# nguyenly.net
KiCad netlist of a schematic drawn in Altium Designer
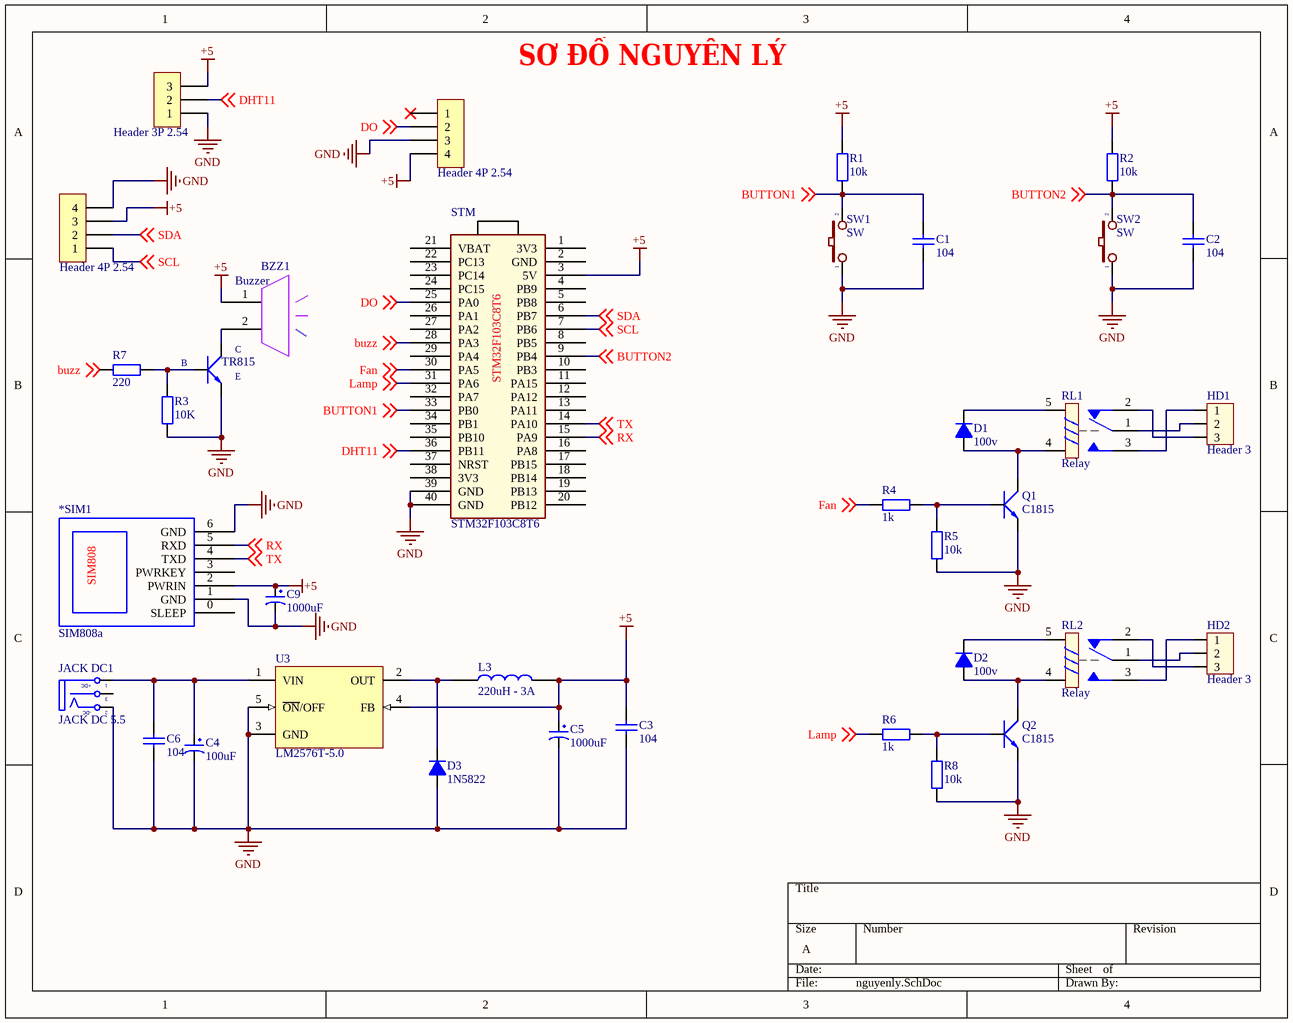
[diagram p0: nguyenly.SchDoc]

(export (version "E")
  (design (tool "Eeschema 10.0.6"))
  (components
    (comp (ref "*SIM1")
      (value "SIM808a")
      (footprint "PCBComponent_1")
      (libsource (lib "SIM808") (part "SIM808a"))
    )
    (comp (ref "BZZ1")
      (value "Buzzer")
      (footprint "buzzer 5V")
      (libsource (lib "My library altium") (part "Buzzer"))
    )
    (comp (ref "C1")
      (value "104")
      (footprint "tu gom")
      (description "Cắm")
      (libsource (lib "Altium_Lib_by_KhueNguyenCreator") (part "Tu gom 104 50V"))
    )
    (comp (ref "C2")
      (value "104")
      (footprint "tu gom")
      (description "Cắm")
      (libsource (lib "Altium_Lib_by_KhueNguyenCreator") (part "Tu gom 104 50V"))
    )
    (comp (ref "C3")
      (value "104")
      (footprint "tu gom")
      (description "Cắm")
      (libsource (lib "Altium_Lib_by_KhueNguyenCreator") (part "Tu gom 104 50V"))
    )
    (comp (ref "C4")
      (value "100uF")
      (footprint "tu hoa 5mm")
      (description "Cắm")
      (libsource (lib "Altium_Lib_by_KhueNguyenCreator") (part "Tu Hoa 100uF 16V 5x7"))
    )
    (comp (ref "C5")
      (value "1000uF")
      (footprint "tu hoa 5mm")
      (description "Cắm")
      (libsource (lib "Altium_Lib_by_KhueNguyenCreator") (part "Tu Hoa 100uF 16V 5x7"))
    )
    (comp (ref "C6")
      (value "104")
      (footprint "tu gom")
      (description "Cắm")
      (libsource (lib "Altium_Lib_by_KhueNguyenCreator") (part "Tu gom 104 50V"))
    )
    (comp (ref "C9")
      (value "1000uF")
      (footprint "tu hoa 13mm")
      (description "Cắm")
      (libsource (lib "Altium_Lib_by_KhueNguyenCreator") (part "Tu Hoa 1000uF 25V 13x21"))
    )
    (comp (ref "D1")
      (value "100v")
      (footprint "DIODE 1A")
      (description "Cắm")
      (libsource (lib "Altium_Lib_by_KhueNguyenCreator") (part "Diode 1N4007"))
    )
    (comp (ref "D2")
      (value "100v")
      (footprint "DIODE 1A")
      (description "Cắm")
      (libsource (lib "Altium_Lib_by_KhueNguyenCreator") (part "Diode 1N4007"))
    )
    (comp (ref "D3")
      (value "1N5822")
      (footprint "D5A")
      (description "Diode 5A")
      (libsource (lib "syhaunguyen") (part "D5A"))
    )
    (comp (ref "H1")
      (value "Header 4P 2.54")
      (footprint "XH2.54M-4")
      (description "Cắm")
      (libsource (lib "Altium_Lib_by_KhueNguyenCreator") (part "Header 4P 2.54 Duc Thang"))
    )
    (comp (ref "H2")
      (value "Header 3P 2.54")
      (footprint "XH2.54M-3")
      (description "Cắm")
      (libsource (lib "Altium_Lib_by_KhueNguyenCreator") (part "Header 3P 2.54 Duc Thang"))
    )
    (comp (ref "H3")
      (value "Header 4P 2.54")
      (footprint "XH2.54M-4")
      (description "Cắm")
      (libsource (lib "") (part "Header 4P 2.54 Duc Thang_1"))
    )
    (comp (ref "HD1")
      (value "Header 3")
      (footprint "HED3")
      (description "Header 3 (Green)")
      (libsource (lib "My library altium") (part "Header 3"))
    )
    (comp (ref "HD2")
      (value "Header 3")
      (footprint "HED3")
      (description "Header 3 (Green)")
      (libsource (lib "My library altium") (part "Header 3"))
    )
    (comp (ref "JACK DC1")
      (value "JACK DC 5.5")
      (footprint "JACK DC 5.5")
      (libsource (lib "Altium_Lib_by_KhueNguyenCreator") (part "JACK DC 5.5"))
    )
    (comp (ref "L3")
      (value "220uH - 3A")
      (footprint "CUON CAM 100uH3A")
      (description "Cắm")
      (libsource (lib "Altium_Lib_by_KhueNguyenCreator") (part "CUON CAM 470uH DIP"))
    )
    (comp (ref "Q1")
      (value "C1815")
      (footprint "TO92")
      (description "NPN transistor")
      (libsource (lib "Altium_Lib_by_KhueNguyenCreator") (part "Trans C1815 DIP"))
    )
    (comp (ref "Q2")
      (value "C1815")
      (footprint "TO92")
      (description "NPN transistor")
      (libsource (lib "Altium_Lib_by_KhueNguyenCreator") (part "Trans C1815 DIP"))
    )
    (comp (ref "R1")
      (value "10k")
      (footprint "tro vach 1/2w")
      (description "Cắm")
      (libsource (lib "Altium_Lib_by_KhueNguyenCreator") (part "Tro Vach 1/2W 5% 1k"))
    )
    (comp (ref "R2")
      (value "10k")
      (footprint "tro vach 1/2w")
      (description "Cắm")
      (libsource (lib "Altium_Lib_by_KhueNguyenCreator") (part "Tro Vach 1/2W 5% 1k"))
    )
    (comp (ref "R3")
      (value "10K")
      (footprint "tro vach 1/2w")
      (description "Cắm")
      (libsource (lib "Altium_Lib_by_KhueNguyenCreator") (part "Tro Vach 1/2W 5% 1k"))
    )
    (comp (ref "R4")
      (value "1k")
      (footprint "tro vach 1/2w")
      (description "Cắm")
      (libsource (lib "Altium_Lib_by_KhueNguyenCreator") (part "Tro Vach 1/2W 5% 1k"))
    )
    (comp (ref "R5")
      (value "10k")
      (footprint "tro vach 1/2w")
      (description "Cắm")
      (libsource (lib "Altium_Lib_by_KhueNguyenCreator") (part "Tro Vach 1/2W 5% 1k"))
    )
    (comp (ref "R6")
      (value "1k")
      (footprint "tro vach 1/2w")
      (description "Cắm")
      (libsource (lib "Altium_Lib_by_KhueNguyenCreator") (part "Tro Vach 1/2W 5% 1k"))
    )
    (comp (ref "R7")
      (value "220")
      (footprint "tro vach 1/2w")
      (description "Cắm")
      (libsource (lib "Altium_Lib_by_KhueNguyenCreator") (part "Tro Vach 1/2W 5% 1k"))
    )
    (comp (ref "R8")
      (value "10k")
      (footprint "tro vach 1/2w")
      (description "Cắm")
      (libsource (lib "Altium_Lib_by_KhueNguyenCreator") (part "Tro Vach 1/2W 5% 1k"))
    )
    (comp (ref "RL1")
      (value "Relay")
      (footprint "Relay 5 Chan SRD")
      (description "Relay 5 Chan")
      (libsource (lib "Altium_Lib_by_KhueNguyenCreator") (part "Relay 5 Chan SRD"))
    )
    (comp (ref "RL2")
      (value "Relay")
      (footprint "Relay 5 Chan SRD")
      (description "Relay 5 Chan")
      (libsource (lib "Altium_Lib_by_KhueNguyenCreator") (part "Relay 5 Chan SRD"))
    )
    (comp (ref "STA.TR1")
      (value "TR815")
      (footprint "QTO-92")
      (description "NPN 600mW, ECB")
      (libsource (lib "My library altium") (part "C1815"))
    )
    (comp (ref "STM")
      (value "STM32F103C8T6")
      (footprint "PCBComponent_1")
      (libsource (lib "STM32F103C8T6") (part "STM32"))
    )
    (comp (ref "SW1")
      (value "SW")
      (footprint "SW2")
      (description "Switch button 2 pin")
      (libsource (lib "syhaunguyen") (part "SW2"))
    )
    (comp (ref "SW2")
      (value "SW")
      (footprint "SW2")
      (description "Switch button 2 pin")
      (libsource (lib "syhaunguyen") (part "SW2"))
    )
    (comp (ref "U3")
      (value "LM2576T-5.0")
      (footprint "LM2576t")
      (description "SIMPLE SWITCHER; 3A Step-Down Voltage Regulator")
      (fields
        (field (name "MANUFACTURER") "National Semiconductor")
        (field (name "DIGIKEYPARTNUMBER") "LM2576T-5.0-ND")
        (field (name "PUBLISHER") "Altium Limited")
      )
      (libsource (lib "My library altium") (part "LM2576T-5.0"))
    )
  )
  (nets
    (net (code "1") (name "+5") (class "Default")
      (node (ref "*SIM1") (pin "2") (pinfunction "PWRIN_2") (pintype "passive"))
      (node (ref "BZZ1") (pin "1") (pinfunction "1_1") (pintype "passive"))
      (node (ref "C3") (pin "1") (pinfunction "1_1") (pintype "passive"))
      (node (ref "C5") (pin "1") (pinfunction "1_1") (pintype "passive"))
      (node (ref "C9") (pin "1") (pinfunction "1_1") (pintype "passive"))
      (node (ref "H1") (pin "4") (pinfunction "4_4") (pintype "passive"))
      (node (ref "H2") (pin "3") (pinfunction "3_3") (pintype "passive"))
      (node (ref "H3") (pin "3") (pinfunction "3_3") (pintype "passive"))
      (node (ref "L3") (pin "2") (pinfunction "2_2") (pintype "passive"))
      (node (ref "R1") (pin "2") (pinfunction "2_2") (pintype "passive"))
      (node (ref "R2") (pin "2") (pinfunction "2_2") (pintype "passive"))
      (node (ref "STM") (pin "3") (pinfunction "5V_3") (pintype "passive"))
      (node (ref "U3") (pin "4") (pinfunction "FB_4") (pintype "input"))
    )
    (net (code "2") (name "BUTTON1") (class "Default")
      (node (ref "C1") (pin "1") (pinfunction "1_1") (pintype "passive"))
      (node (ref "R1") (pin "1") (pinfunction "1_1") (pintype "passive"))
      (node (ref "STM") (pin "33") (pinfunction "PB0_33") (pintype "passive"))
      (node (ref "SW1") (pin "2") (pinfunction "2_2") (pintype "passive"))
    )
    (net (code "3") (name "BUTTON2") (class "Default")
      (node (ref "C2") (pin "1") (pinfunction "1_1") (pintype "passive"))
      (node (ref "R2") (pin "1") (pinfunction "1_1") (pintype "passive"))
      (node (ref "STM") (pin "9") (pinfunction "PB4_9") (pintype "passive"))
      (node (ref "SW2") (pin "2") (pinfunction "2_2") (pintype "passive"))
    )
    (net (code "4") (name "DHT11") (class "Default")
      (node (ref "H2") (pin "2") (pinfunction "2_2") (pintype "passive"))
      (node (ref "STM") (pin "36") (pinfunction "PB11_36") (pintype "passive"))
    )
    (net (code "5") (name "DO") (class "Default")
      (node (ref "H1") (pin "2") (pinfunction "2_2") (pintype "passive"))
      (node (ref "STM") (pin "25") (pinfunction "PA0_25") (pintype "passive"))
    )
    (net (code "6") (name "Fan") (class "Default")
      (node (ref "R4") (pin "1") (pinfunction "1_1") (pintype "passive"))
      (node (ref "STM") (pin "30") (pinfunction "PA5_30") (pintype "passive"))
    )
    (net (code "7") (name "GND") (class "Default")
      (node (ref "*SIM1") (pin "1") (pinfunction "GND_1") (pintype "passive"))
      (node (ref "*SIM1") (pin "6") (pinfunction "GND_6") (pintype "passive"))
      (node (ref "C1") (pin "2") (pinfunction "2_2") (pintype "passive"))
      (node (ref "C2") (pin "2") (pinfunction "2_2") (pintype "passive"))
      (node (ref "C3") (pin "2") (pinfunction "2_2") (pintype "passive"))
      (node (ref "C4") (pin "2") (pinfunction "2_2") (pintype "passive"))
      (node (ref "C5") (pin "2") (pinfunction "2_2") (pintype "passive"))
      (node (ref "C6") (pin "2") (pinfunction "2_2") (pintype "passive"))
      (node (ref "C9") (pin "2") (pinfunction "2_2") (pintype "passive"))
      (node (ref "D3") (pin "1") (pinfunction "A_1") (pintype "passive"))
      (node (ref "H1") (pin "3") (pinfunction "3_3") (pintype "passive"))
      (node (ref "H2") (pin "1") (pinfunction "1_1") (pintype "passive"))
      (node (ref "H3") (pin "4") (pinfunction "4_4") (pintype "passive"))
      (node (ref "JACK DC1") (pin "2") (pinfunction "TN_2") (pintype "passive"))
      (node (ref "Q1") (pin "1") (pinfunction "E_1") (pintype "passive"))
      (node (ref "Q2") (pin "1") (pinfunction "E_1") (pintype "passive"))
      (node (ref "R3") (pin "1") (pinfunction "1_1") (pintype "passive"))
      (node (ref "R5") (pin "1") (pinfunction "1_1") (pintype "passive"))
      (node (ref "R8") (pin "1") (pinfunction "1_1") (pintype "passive"))
      (node (ref "STA.TR1") (pin "1") (pinfunction "E_1") (pintype "passive"))
      (node (ref "STM") (pin "39") (pinfunction "GND_39") (pintype "passive"))
      (node (ref "STM") (pin "40") (pinfunction "GND_40") (pintype "passive"))
      (node (ref "SW1") (pin "1") (pinfunction "1_1") (pintype "passive"))
      (node (ref "SW2") (pin "1") (pinfunction "1_1") (pintype "passive"))
      (node (ref "U3") (pin "3") (pinfunction "GND_3") (pintype "power_in"))
      (node (ref "U3") (pin "5") (pinfunction "~{ON}/OFF_5") (pintype "input"))
    )
    (net (code "8") (name "Lamp") (class "Default")
      (node (ref "R6") (pin "1") (pinfunction "1_1") (pintype "passive"))
      (node (ref "STM") (pin "31") (pinfunction "PA6_31") (pintype "passive"))
    )
    (net (code "9") (name "Net-(D1-A)") (class "Default")
      (node (ref "D1") (pin "1") (pinfunction "A_1") (pintype "passive"))
      (node (ref "Q1") (pin "2") (pinfunction "C_2") (pintype "passive"))
      (node (ref "RL1") (pin "4") (pinfunction "4_4") (pintype "passive"))
    )
    (net (code "10") (name "Net-(D1-K)") (class "Default")
      (node (ref "D1") (pin "2") (pinfunction "K_2") (pintype "passive"))
      (node (ref "RL1") (pin "5") (pinfunction "5_5") (pintype "passive"))
    )
    (net (code "11") (name "Net-(D2-A)") (class "Default")
      (node (ref "D2") (pin "1") (pinfunction "A_1") (pintype "passive"))
      (node (ref "Q2") (pin "2") (pinfunction "C_2") (pintype "passive"))
      (node (ref "RL2") (pin "4") (pinfunction "4_4") (pintype "passive"))
    )
    (net (code "12") (name "Net-(D2-K)") (class "Default")
      (node (ref "D2") (pin "2") (pinfunction "K_2") (pintype "passive"))
      (node (ref "RL2") (pin "5") (pinfunction "5_5") (pintype "passive"))
    )
    (net (code "13") (name "Net-(D3-K)") (class "Default")
      (node (ref "D3") (pin "2") (pinfunction "K_2") (pintype "passive"))
      (node (ref "L3") (pin "1") (pinfunction "1_1") (pintype "passive"))
      (node (ref "U3") (pin "2") (pinfunction "OUT_2") (pintype "power_in"))
    )
    (net (code "14") (name "Net-(HD1-Pad1)") (class "Default")
      (node (ref "HD1") (pin "1") (pinfunction "1_1") (pintype "passive"))
      (node (ref "RL1") (pin "3") (pinfunction "3_3") (pintype "passive"))
    )
    (net (code "15") (name "Net-(HD1-Pad2)") (class "Default")
      (node (ref "HD1") (pin "2") (pinfunction "2_2") (pintype "passive"))
      (node (ref "RL1") (pin "1") (pinfunction "1_1") (pintype "passive"))
    )
    (net (code "16") (name "Net-(HD1-Pad3)") (class "Default")
      (node (ref "HD1") (pin "3") (pinfunction "3_3") (pintype "passive"))
      (node (ref "RL1") (pin "2") (pinfunction "2_2") (pintype "passive"))
    )
    (net (code "17") (name "Net-(HD2-Pad1)") (class "Default")
      (node (ref "HD2") (pin "1") (pinfunction "1_1") (pintype "passive"))
      (node (ref "RL2") (pin "3") (pinfunction "3_3") (pintype "passive"))
    )
    (net (code "18") (name "Net-(HD2-Pad2)") (class "Default")
      (node (ref "HD2") (pin "2") (pinfunction "2_2") (pintype "passive"))
      (node (ref "RL2") (pin "1") (pinfunction "1_1") (pintype "passive"))
    )
    (net (code "19") (name "Net-(HD2-Pad3)") (class "Default")
      (node (ref "HD2") (pin "3") (pinfunction "3_3") (pintype "passive"))
      (node (ref "RL2") (pin "2") (pinfunction "2_2") (pintype "passive"))
    )
    (net (code "20") (name "Net-(JACK DC1-T)") (class "Default")
      (node (ref "C4") (pin "1") (pinfunction "1_1") (pintype "passive"))
      (node (ref "C6") (pin "1") (pinfunction "1_1") (pintype "passive"))
      (node (ref "JACK DC1") (pin "1") (pinfunction "T_1") (pintype "passive"))
      (node (ref "U3") (pin "1") (pinfunction "VIN_1") (pintype "power_in"))
    )
    (net (code "21") (name "Net-(Q1-B)") (class "Default")
      (node (ref "Q1") (pin "3") (pinfunction "B_3") (pintype "passive"))
      (node (ref "R4") (pin "2") (pinfunction "2_2") (pintype "passive"))
      (node (ref "R5") (pin "2") (pinfunction "2_2") (pintype "passive"))
    )
    (net (code "22") (name "Net-(Q2-B)") (class "Default")
      (node (ref "Q2") (pin "3") (pinfunction "B_3") (pintype "passive"))
      (node (ref "R6") (pin "2") (pinfunction "2_2") (pintype "passive"))
      (node (ref "R8") (pin "2") (pinfunction "2_2") (pintype "passive"))
    )
    (net (code "23") (name "Net-(STA.TR1-B)") (class "Default")
      (node (ref "R3") (pin "2") (pinfunction "2_2") (pintype "passive"))
      (node (ref "R7") (pin "2") (pinfunction "2_2") (pintype "passive"))
      (node (ref "STA.TR1") (pin "3") (pinfunction "B_3") (pintype "passive"))
    )
    (net (code "24") (name "Net-(STA.TR1-C)") (class "Default")
      (node (ref "BZZ1") (pin "2") (pinfunction "2_2") (pintype "passive"))
      (node (ref "STA.TR1") (pin "2") (pinfunction "C_2") (pintype "passive"))
    )
    (net (code "25") (name "RX") (class "Default")
      (node (ref "*SIM1") (pin "5") (pinfunction "RXD_5") (pintype "passive"))
      (node (ref "STM") (pin "15") (pinfunction "PA9_15") (pintype "passive"))
    )
    (net (code "26") (name "SCL") (class "Default")
      (node (ref "H3") (pin "1") (pinfunction "1_1") (pintype "passive"))
      (node (ref "STM") (pin "7") (pinfunction "PB6_7") (pintype "passive"))
    )
    (net (code "27") (name "SDA") (class "Default")
      (node (ref "H3") (pin "2") (pinfunction "2_2") (pintype "passive"))
      (node (ref "STM") (pin "6") (pinfunction "PB7_6") (pintype "passive"))
    )
    (net (code "28") (name "TX") (class "Default")
      (node (ref "*SIM1") (pin "4") (pinfunction "TXD_4") (pintype "passive"))
      (node (ref "STM") (pin "14") (pinfunction "PA10_14") (pintype "passive"))
    )
    (net (code "29") (name "buzz") (class "Default")
      (node (ref "R7") (pin "1") (pinfunction "1_1") (pintype "passive"))
      (node (ref "STM") (pin "28") (pinfunction "PA3_28") (pintype "passive"))
    )
    (net (code "30") (name "unconnected-(*SIM1-PWRKEY-Pad3)") (class "Default")
      (node (ref "*SIM1") (pin "3") (pinfunction "PWRKEY_3") (pintype "passive"))
    )
    (net (code "31") (name "unconnected-(*SIM1-SLEEP-Pad0)") (class "Default")
      (node (ref "*SIM1") (pin "0") (pinfunction "SLEEP_0") (pintype "passive"))
    )
    (net (code "32") (name "unconnected-(H1-Pad1)") (class "Default")
      (node (ref "H1") (pin "1") (pinfunction "1_1") (pintype "passive+no_connect"))
    )
    (net (code "33") (name "unconnected-(JACK DC1-S-Pad3)") (class "Default")
      (node (ref "JACK DC1") (pin "3") (pinfunction "S_3") (pintype "power_in"))
    )
    (net (code "34") (name "unconnected-(STM-3V3-Pad1)") (class "Default")
      (node (ref "STM") (pin "1") (pinfunction "3V3_1") (pintype "passive"))
    )
    (net (code "35") (name "unconnected-(STM-3V3-Pad38)") (class "Default")
      (node (ref "STM") (pin "38") (pinfunction "3V3_38") (pintype "passive"))
    )
    (net (code "36") (name "unconnected-(STM-GND-Pad2)") (class "Default")
      (node (ref "STM") (pin "2") (pinfunction "GND_2") (pintype "passive"))
    )
    (net (code "37") (name "unconnected-(STM-NRST-Pad37)") (class "Default")
      (node (ref "STM") (pin "37") (pinfunction "NRST_37") (pintype "passive"))
    )
    (net (code "38") (name "unconnected-(STM-PA1-Pad26)") (class "Default")
      (node (ref "STM") (pin "26") (pinfunction "PA1_26") (pintype "passive"))
    )
    (net (code "39") (name "unconnected-(STM-PA2-Pad27)") (class "Default")
      (node (ref "STM") (pin "27") (pinfunction "PA2_27") (pintype "passive"))
    )
    (net (code "40") (name "unconnected-(STM-PA4-Pad29)") (class "Default")
      (node (ref "STM") (pin "29") (pinfunction "PA4_29") (pintype "passive"))
    )
    (net (code "41") (name "unconnected-(STM-PA7-Pad32)") (class "Default")
      (node (ref "STM") (pin "32") (pinfunction "PA7_32") (pintype "passive"))
    )
    (net (code "42") (name "unconnected-(STM-PA8-Pad16)") (class "Default")
      (node (ref "STM") (pin "16") (pinfunction "PA8_16") (pintype "passive"))
    )
    (net (code "43") (name "unconnected-(STM-PA11-Pad13)") (class "Default")
      (node (ref "STM") (pin "13") (pinfunction "PA11_13") (pintype "passive"))
    )
    (net (code "44") (name "unconnected-(STM-PA12-Pad12)") (class "Default")
      (node (ref "STM") (pin "12") (pinfunction "PA12_12") (pintype "passive"))
    )
    (net (code "45") (name "unconnected-(STM-PA15-Pad11)") (class "Default")
      (node (ref "STM") (pin "11") (pinfunction "PA15_11") (pintype "passive"))
    )
    (net (code "46") (name "unconnected-(STM-PB1-Pad34)") (class "Default")
      (node (ref "STM") (pin "34") (pinfunction "PB1_34") (pintype "passive"))
    )
    (net (code "47") (name "unconnected-(STM-PB3-Pad10)") (class "Default")
      (node (ref "STM") (pin "10") (pinfunction "PB3_10") (pintype "passive"))
    )
    (net (code "48") (name "unconnected-(STM-PB5-Pad8)") (class "Default")
      (node (ref "STM") (pin "8") (pinfunction "PB5_8") (pintype "passive"))
    )
    (net (code "49") (name "unconnected-(STM-PB8-Pad5)") (class "Default")
      (node (ref "STM") (pin "5") (pinfunction "PB8_5") (pintype "passive"))
    )
    (net (code "50") (name "unconnected-(STM-PB9-Pad4)") (class "Default")
      (node (ref "STM") (pin "4") (pinfunction "PB9_4") (pintype "passive"))
    )
    (net (code "51") (name "unconnected-(STM-PB10-Pad35)") (class "Default")
      (node (ref "STM") (pin "35") (pinfunction "PB10_35") (pintype "passive"))
    )
    (net (code "52") (name "unconnected-(STM-PB12-Pad20)") (class "Default")
      (node (ref "STM") (pin "20") (pinfunction "PB12_20") (pintype "passive"))
    )
    (net (code "53") (name "unconnected-(STM-PB13-Pad19)") (class "Default")
      (node (ref "STM") (pin "19") (pinfunction "PB13_19") (pintype "passive"))
    )
    (net (code "54") (name "unconnected-(STM-PB14-Pad18)") (class "Default")
      (node (ref "STM") (pin "18") (pinfunction "PB14_18") (pintype "passive"))
    )
    (net (code "55") (name "unconnected-(STM-PB15-Pad17)") (class "Default")
      (node (ref "STM") (pin "17") (pinfunction "PB15_17") (pintype "passive"))
    )
    (net (code "56") (name "unconnected-(STM-PC13-Pad22)") (class "Default")
      (node (ref "STM") (pin "22") (pinfunction "PC13_22") (pintype "passive"))
    )
    (net (code "57") (name "unconnected-(STM-PC14-Pad23)") (class "Default")
      (node (ref "STM") (pin "23") (pinfunction "PC14_23") (pintype "passive"))
    )
    (net (code "58") (name "unconnected-(STM-PC15-Pad24)") (class "Default")
      (node (ref "STM") (pin "24") (pinfunction "PC15_24") (pintype "passive"))
    )
    (net (code "59") (name "unconnected-(STM-VBAT-Pad21)") (class "Default")
      (node (ref "STM") (pin "21") (pinfunction "VBAT_21") (pintype "passive"))
    )
  )
)
